# AD_Sensor_Module_-_SC.net
KiCad netlist of a schematic drawn in Altium Designer
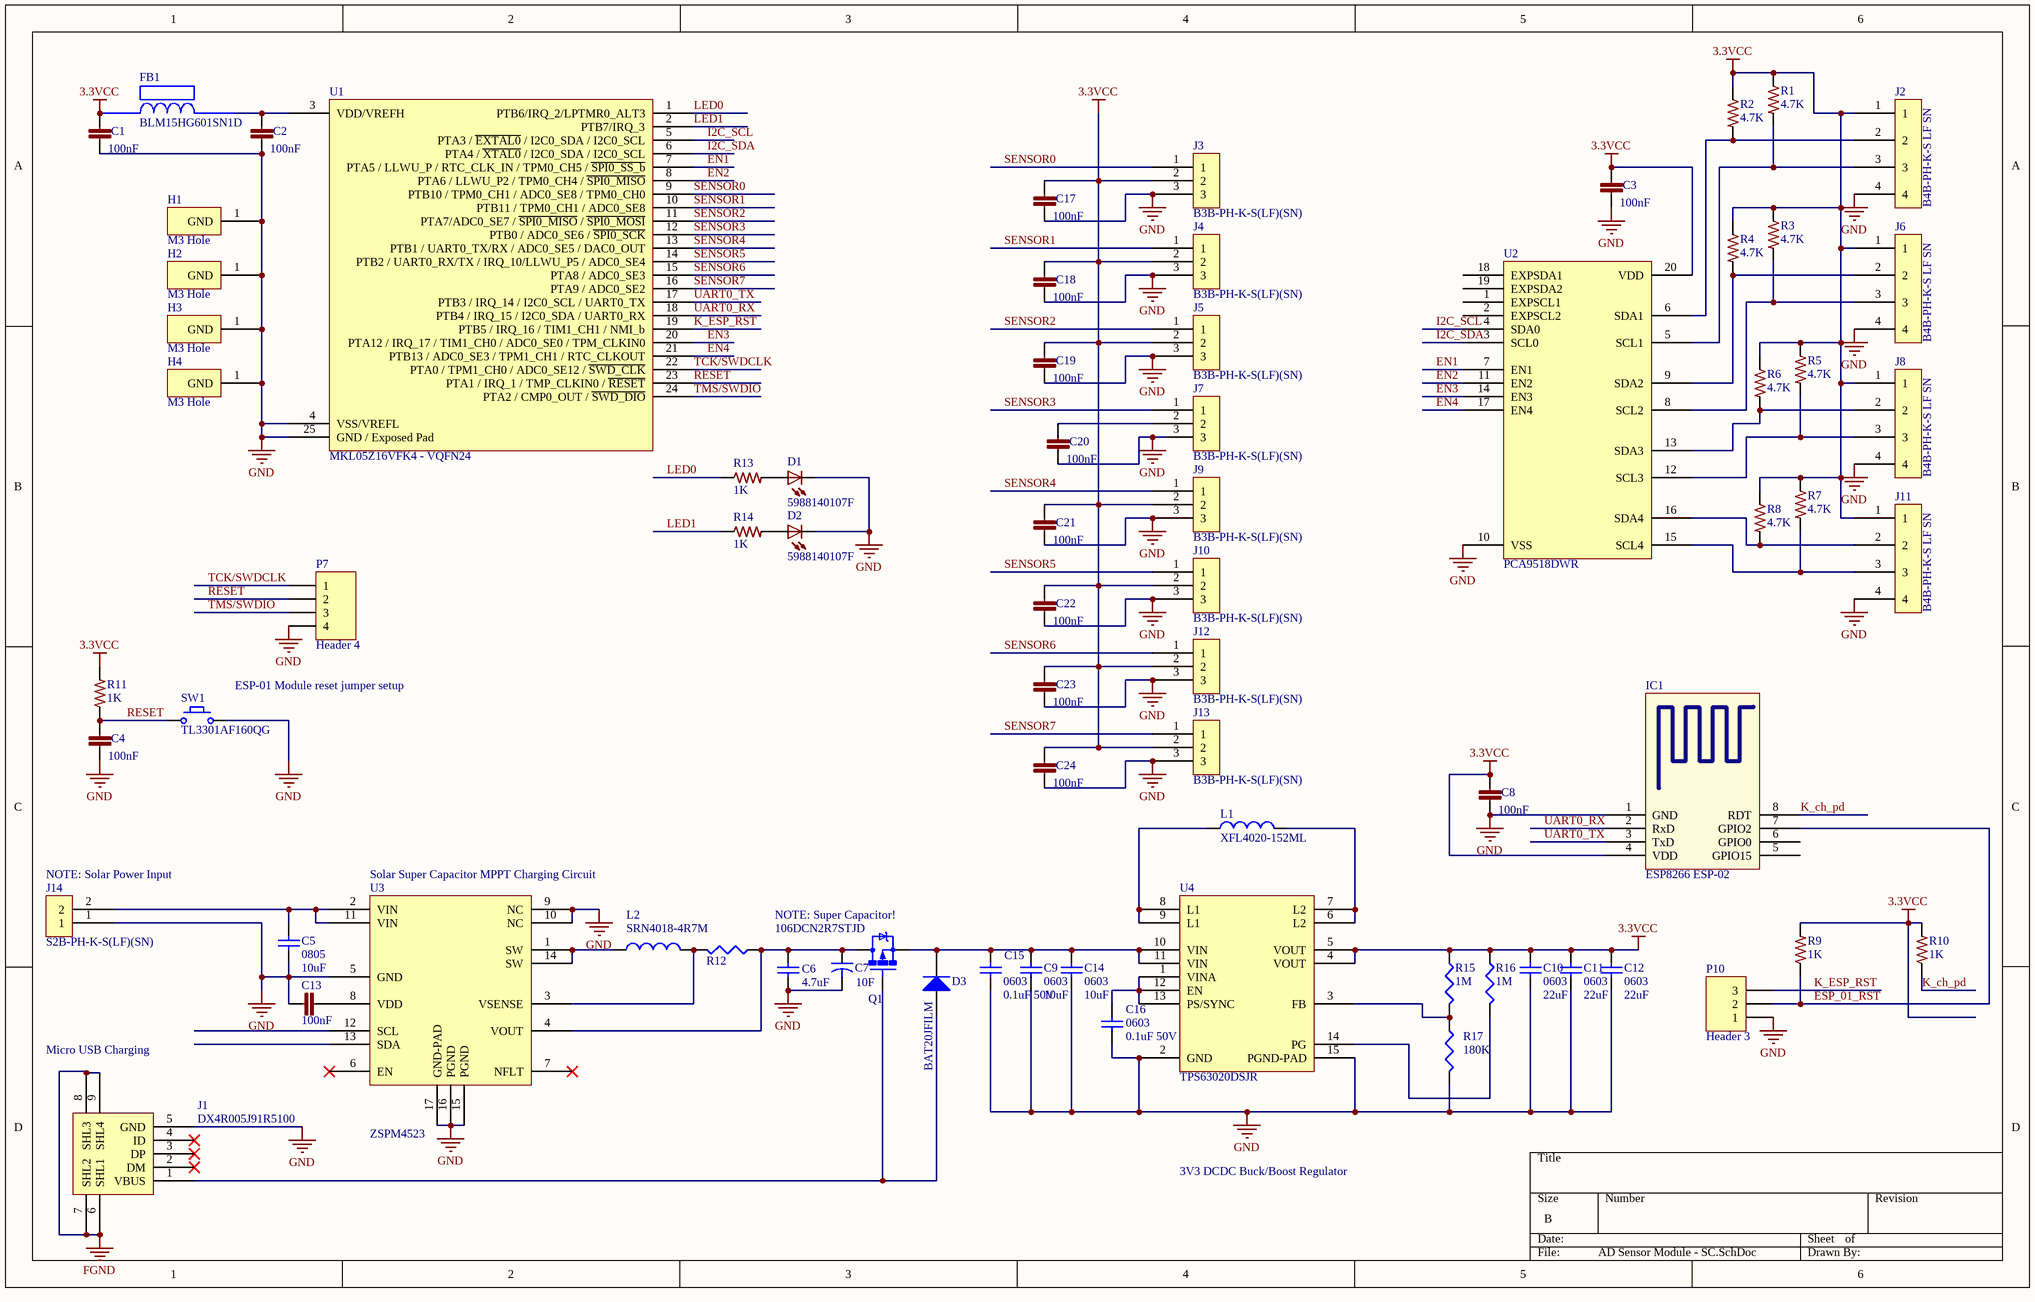
[diagram p0: AD Sensor Module - SC.SchDoc]

(export (version "E")
  (design (tool "Eeschema 10.0.6"))
  (components
    (comp (ref "C1")
      (value "100nF")
      (footprint "C0402")
      (description "CAP CER 0402 100nF 16V 10% X7R")
      (fields
        (field (name "MANUFACTURERPARTNUMBER") "GRM155R71C104KA88D")
        (field (name "PUBLISHER") "UltiMachine")
      )
      (libsource (lib "3Delight") (part "GRM155R71C104KA88D"))
    )
    (comp (ref "C2")
      (value "100nF")
      (footprint "C0402")
      (description "CAP CER 0402 100nF 16V 10% X7R")
      (fields
        (field (name "MANUFACTURERPARTNUMBER") "GRM155R71C104KA88D")
        (field (name "PUBLISHER") "UltiMachine")
      )
      (libsource (lib "3Delight") (part "GRM155R71C104KA88D"))
    )
    (comp (ref "C3")
      (value "100nF")
      (footprint "C0402")
      (description "CAP CER 0402 100nF 16V 10% X7R")
      (fields
        (field (name "MANUFACTURERPARTNUMBER") "GRM155R71C104KA88D")
        (field (name "PUBLISHER") "UltiMachine")
      )
      (libsource (lib "3Delight") (part "GRM155R71C104KA88D"))
    )
    (comp (ref "C4")
      (value "100nF")
      (footprint "C0402")
      (description "CAP CER 0402 100nF 16V 10% X7R")
      (fields
        (field (name "MANUFACTURERPARTNUMBER") "GRM155R71C104KA88D")
        (field (name "PUBLISHER") "UltiMachine")
      )
      (libsource (lib "3Delight") (part "GRM155R71C104KA88D"))
    )
    (comp (ref "C5")
      (value "0805")
      (footprint "C0805")
      (description "CAP CER 10UF 10V X5R 0805")
      (fields
        (field (name "MFR") "Samsung Electro-Mechanics America, Inc.")
        (field (name "TOLERANCE") "10%")
        (field (name "ALTIUM_VALUE") "10uF")
        (field (name "DESIGNER") "Adam Vadala-Roth")
      )
      (libsource (lib "Sensor Package") (part "CL21A106KPCLQNC"))
    )
    (comp (ref "C6")
      (value "4.7uF")
      (footprint "C0805")
      (description "CAP CER 4.7UF 10V Y5V 0805")
      (fields
        (field (name "MFR") "Samsung Electro-Mechanics America, Inc.")
        (field (name "TOLERANCE") "20%")
        (field (name "DESIGNER") "Adam Vadala-Roth")
      )
      (libsource (lib "Sensor Package") (part "CL21F475ZPFNNNE"))
    )
    (comp (ref "C7")
      (value "106DCN2R7STJD")
      (footprint "106DCN2R7STJD")
      (description "CAP 10F -20%, +50% 2.7V T/H")
      (fields
        (field (name "MFR") "Illinois Capacitor")
        (field (name "TOLERANCE") "20%")
        (field (name "ALTIUM_VALUE") "10F")
        (field (name "DESIGNER") "Adam Vadala-Roth")
      )
      (libsource (lib "Sensor Package") (part "106DCN2R7STJD"))
    )
    (comp (ref "C8")
      (value "100nF")
      (footprint "C0402")
      (description "CAP CER 0402 100nF 16V 10% X7R")
      (fields
        (field (name "MANUFACTURERPARTNUMBER") "GRM155R71C104KA88D")
        (field (name "PUBLISHER") "UltiMachine")
      )
      (libsource (lib "3Delight") (part "GRM155R71C104KA88D"))
    )
    (comp (ref "C9")
      (value "0603")
      (footprint "C0603")
      (description "CAP CER 10UF 6.3V X5R 0603")
      (fields
        (field (name "MFR") "Samsung Electro-Mechanics America, Inc.")
        (field (name "TOLERANCE") "10%")
        (field (name "ALTIUM_VALUE") "10uF")
        (field (name "DESIGNER") "Adam Vadala-Roth")
      )
      (libsource (lib "Sensor Package") (part "CL10A106KQ8NNNC"))
    )
    (comp (ref "C10")
      (value "0603")
      (footprint "C0603")
      (description "CAP CER 22UF 6.3V X5R 0603")
      (fields
        (field (name "MFR") "Samsung Electro-Mechanics America, Inc.")
        (field (name "TOLERANCE") "10%")
        (field (name "ALTIUM_VALUE") "22uF")
        (field (name "DESIGNER") "Adam Vadala-Roth")
      )
      (libsource (lib "Sensor Package") (part "CL10A226KQ8NRNE"))
    )
    (comp (ref "C11")
      (value "0603")
      (footprint "C0603")
      (description "CAP CER 22UF 6.3V X5R 0603")
      (fields
        (field (name "MFR") "Samsung Electro-Mechanics America, Inc.")
        (field (name "TOLERANCE") "10%")
        (field (name "ALTIUM_VALUE") "22uF")
        (field (name "DESIGNER") "Adam Vadala-Roth")
      )
      (libsource (lib "Sensor Package") (part "CL10A226KQ8NRNE"))
    )
    (comp (ref "C12")
      (value "0603")
      (footprint "C0603")
      (description "CAP CER 22UF 6.3V X5R 0603")
      (fields
        (field (name "MFR") "Samsung Electro-Mechanics America, Inc.")
        (field (name "TOLERANCE") "10%")
        (field (name "ALTIUM_VALUE") "22uF")
        (field (name "DESIGNER") "Adam Vadala-Roth")
      )
      (libsource (lib "Sensor Package") (part "CL10A226KQ8NRNE"))
    )
    (comp (ref "C13")
      (value "100nF")
      (footprint "C0402")
      (description "CAP CER 0402 100nF 16V 10% X7R")
      (fields
        (field (name "MANUFACTURERPARTNUMBER") "GRM155R71C104KA88D")
        (field (name "PUBLISHER") "UltiMachine")
      )
      (libsource (lib "") (part "GRM155R71C104KA88D_1"))
    )
    (comp (ref "C14")
      (value "0603")
      (footprint "C0603")
      (description "CAP CER 10UF 6.3V X5R 0603")
      (fields
        (field (name "MFR") "Samsung Electro-Mechanics America, Inc.")
        (field (name "TOLERANCE") "10%")
        (field (name "ALTIUM_VALUE") "10uF")
        (field (name "DESIGNER") "Adam Vadala-Roth")
      )
      (libsource (lib "Sensor Package") (part "CL10A106KQ8NNNC"))
    )
    (comp (ref "C15")
      (value "0603")
      (footprint "C0603")
      (description "CAP CER 0.1UF 50V 10% X7R 0603")
      (fields
        (field (name "MFR PART #") "CL10B104KB8SFNC")
        (field (name "MFR") "Samsung")
        (field (name "ALTIUM_VALUE") "0.1uF 50V")
      )
      (libsource (lib "Sensor Package") (part "CL10B104KB8SFNC"))
    )
    (comp (ref "C16")
      (value "0603")
      (footprint "C0603")
      (description "CAP CER 0.1UF 50V 10% X7R 0603")
      (fields
        (field (name "MFR PART #") "CL10B104KB8SFNC")
        (field (name "MFR") "Samsung")
        (field (name "ALTIUM_VALUE") "0.1uF 50V")
      )
      (libsource (lib "Sensor Package") (part "CL10B104KB8SFNC"))
    )
    (comp (ref "C17")
      (value "100nF")
      (footprint "C0402")
      (description "CAP CER 0402 100nF 16V 10% X7R")
      (fields
        (field (name "MANUFACTURERPARTNUMBER") "GRM155R71C104KA88D")
        (field (name "PUBLISHER") "UltiMachine")
      )
      (libsource (lib "3Delight") (part "GRM155R71C104KA88D"))
    )
    (comp (ref "C18")
      (value "100nF")
      (footprint "C0402")
      (description "CAP CER 0402 100nF 16V 10% X7R")
      (fields
        (field (name "MANUFACTURERPARTNUMBER") "GRM155R71C104KA88D")
        (field (name "PUBLISHER") "UltiMachine")
      )
      (libsource (lib "3Delight") (part "GRM155R71C104KA88D"))
    )
    (comp (ref "C19")
      (value "100nF")
      (footprint "C0402")
      (description "CAP CER 0402 100nF 16V 10% X7R")
      (fields
        (field (name "MANUFACTURERPARTNUMBER") "GRM155R71C104KA88D")
        (field (name "PUBLISHER") "UltiMachine")
      )
      (libsource (lib "3Delight") (part "GRM155R71C104KA88D"))
    )
    (comp (ref "C20")
      (value "100nF")
      (footprint "C0402")
      (description "CAP CER 0402 100nF 16V 10% X7R")
      (fields
        (field (name "MANUFACTURERPARTNUMBER") "GRM155R71C104KA88D")
        (field (name "PUBLISHER") "UltiMachine")
      )
      (libsource (lib "3Delight") (part "GRM155R71C104KA88D"))
    )
    (comp (ref "C21")
      (value "100nF")
      (footprint "C0402")
      (description "CAP CER 0402 100nF 16V 10% X7R")
      (fields
        (field (name "MANUFACTURERPARTNUMBER") "GRM155R71C104KA88D")
        (field (name "PUBLISHER") "UltiMachine")
      )
      (libsource (lib "3Delight") (part "GRM155R71C104KA88D"))
    )
    (comp (ref "C22")
      (value "100nF")
      (footprint "C0402")
      (description "CAP CER 0402 100nF 16V 10% X7R")
      (fields
        (field (name "MANUFACTURERPARTNUMBER") "GRM155R71C104KA88D")
        (field (name "PUBLISHER") "UltiMachine")
      )
      (libsource (lib "3Delight") (part "GRM155R71C104KA88D"))
    )
    (comp (ref "C23")
      (value "100nF")
      (footprint "C0402")
      (description "CAP CER 0402 100nF 16V 10% X7R")
      (fields
        (field (name "MANUFACTURERPARTNUMBER") "GRM155R71C104KA88D")
        (field (name "PUBLISHER") "UltiMachine")
      )
      (libsource (lib "3Delight") (part "GRM155R71C104KA88D"))
    )
    (comp (ref "C24")
      (value "100nF")
      (footprint "C0402")
      (description "CAP CER 0402 100nF 16V 10% X7R")
      (fields
        (field (name "MANUFACTURERPARTNUMBER") "GRM155R71C104KA88D")
        (field (name "PUBLISHER") "UltiMachine")
      )
      (libsource (lib "3Delight") (part "GRM155R71C104KA88D"))
    )
    (comp (ref "D1")
      (value "5988140107F")
      (footprint "LED2012120")
      (description "LED 0805 Yellow")
      (fields (field (name "PUBLISHER") "UltiMachine"))
      (libsource (lib "Tigershark3D") (part "5988140107F"))
    )
    (comp (ref "D2")
      (value "5988140107F")
      (footprint "LED2012120")
      (description "LED 0805 Yellow")
      (fields (field (name "PUBLISHER") "UltiMachine"))
      (libsource (lib "Tigershark3D") (part "5988140107F"))
    )
    (comp (ref "D3")
      (value "BAT20JFILM")
      (footprint "BAT20JFILM - DIOM1712X11N")
      (description "DIODE SCHOTTKY 23V 1A SOD323")
      (fields
        (field (name "MFR") "ST Microelectronics")
        (field (name "PUBLISHER") "Altium Limited")
        (field (name "DESIGNER") "Adam J Valala-Roth")
      )
      (libsource (lib "Sensor Package") (part "BAT20JFILM"))
    )
    (comp (ref "FB1")
      (value "BLM15HG601SN1D")
      (footprint "BLM18PG121SN1D")
      (libsource (lib "Sensor Package") (part "BLM15HG601SN1D"))
    )
    (comp (ref "H1")
      (value "M3 Hole")
      (footprint "Hole-3mm")
      (description "3mm Hole")
      (libsource (lib "Sensor Package") (part "Hole"))
    )
    (comp (ref "H2")
      (value "M3 Hole")
      (footprint "Hole-3mm")
      (description "3mm Hole")
      (libsource (lib "Sensor Package") (part "Hole"))
    )
    (comp (ref "H3")
      (value "M3 Hole")
      (footprint "Hole-3mm")
      (description "3mm Hole")
      (libsource (lib "Sensor Package") (part "Hole"))
    )
    (comp (ref "H4")
      (value "M3 Hole")
      (footprint "Hole-3mm")
      (description "3mm Hole")
      (libsource (lib "Sensor Package") (part "Hole"))
    )
    (comp (ref "IC1")
      (value "ESP8266 ESP-02")
      (footprint "ESP8266 ESP-02")
      (libsource (lib "ESP8266") (part "ESP8266 ESP-02"))
    )
    (comp (ref "J1")
      (value "DX4R005J91R5100")
      (footprint "Micro USB Circular Holes Only")
      (description "Micro USB Jack B")
      (libsource (lib "Sensor Package") (part "Micro USB"))
    )
    (comp (ref "J2")
      (value "B4B-PH-K-S LF SN")
      (footprint "B4B-PH-K-S(LF)(SN)")
      (description "CONN HEADER PH TOP 4POS 2MM")
      (fields (field (name "MFR") "JST") (field (name "DESIGNER") "Adam Vadala-Roth"))
      (libsource (lib "Sensor Package") (part "B4B-PH-K-S LF SN"))
    )
    (comp (ref "J3")
      (value "B3B-PH-K-S(LF)(SN)")
      (footprint "B3B-PH-K-S(LF)(SN)")
      (description "CONN HEADER PH TOP 3POS 2MM")
      (fields (field (name "MFR") "JST") (field (name "DESIGNER") "Adam Vadala-Roth"))
      (libsource (lib "Sensor Package") (part "B3B-PH-K-S(LF)(SN)"))
    )
    (comp (ref "J4")
      (value "B3B-PH-K-S(LF)(SN)")
      (footprint "B3B-PH-K-S(LF)(SN)")
      (description "CONN HEADER PH TOP 3POS 2MM")
      (fields (field (name "MFR") "JST") (field (name "DESIGNER") "Adam Vadala-Roth"))
      (libsource (lib "Sensor Package") (part "B3B-PH-K-S(LF)(SN)"))
    )
    (comp (ref "J5")
      (value "B3B-PH-K-S(LF)(SN)")
      (footprint "B3B-PH-K-S(LF)(SN)")
      (description "CONN HEADER PH TOP 3POS 2MM")
      (fields (field (name "MFR") "JST") (field (name "DESIGNER") "Adam Vadala-Roth"))
      (libsource (lib "Sensor Package") (part "B3B-PH-K-S(LF)(SN)"))
    )
    (comp (ref "J6")
      (value "B4B-PH-K-S LF SN")
      (footprint "B4B-PH-K-S(LF)(SN)")
      (description "CONN HEADER PH TOP 4POS 2MM")
      (fields (field (name "MFR") "JST") (field (name "DESIGNER") "Adam Vadala-Roth"))
      (libsource (lib "Sensor Package") (part "B4B-PH-K-S LF SN"))
    )
    (comp (ref "J7")
      (value "B3B-PH-K-S(LF)(SN)")
      (footprint "B3B-PH-K-S(LF)(SN)")
      (description "CONN HEADER PH TOP 3POS 2MM")
      (fields (field (name "MFR") "JST") (field (name "DESIGNER") "Adam Vadala-Roth"))
      (libsource (lib "Sensor Package") (part "B3B-PH-K-S(LF)(SN)"))
    )
    (comp (ref "J8")
      (value "B4B-PH-K-S LF SN")
      (footprint "B4B-PH-K-S(LF)(SN)")
      (description "CONN HEADER PH TOP 4POS 2MM")
      (fields (field (name "MFR") "JST") (field (name "DESIGNER") "Adam Vadala-Roth"))
      (libsource (lib "Sensor Package") (part "B4B-PH-K-S LF SN"))
    )
    (comp (ref "J9")
      (value "B3B-PH-K-S(LF)(SN)")
      (footprint "B3B-PH-K-S(LF)(SN)")
      (description "CONN HEADER PH TOP 3POS 2MM")
      (fields (field (name "MFR") "JST") (field (name "DESIGNER") "Adam Vadala-Roth"))
      (libsource (lib "Sensor Package") (part "B3B-PH-K-S(LF)(SN)"))
    )
    (comp (ref "J10")
      (value "B3B-PH-K-S(LF)(SN)")
      (footprint "B3B-PH-K-S(LF)(SN)")
      (description "CONN HEADER PH TOP 3POS 2MM")
      (fields (field (name "MFR") "JST") (field (name "DESIGNER") "Adam Vadala-Roth"))
      (libsource (lib "Sensor Package") (part "B3B-PH-K-S(LF)(SN)"))
    )
    (comp (ref "J11")
      (value "B4B-PH-K-S LF SN")
      (footprint "B4B-PH-K-S(LF)(SN)")
      (description "CONN HEADER PH TOP 4POS 2MM")
      (fields (field (name "MFR") "JST") (field (name "DESIGNER") "Adam Vadala-Roth"))
      (libsource (lib "Sensor Package") (part "B4B-PH-K-S LF SN"))
    )
    (comp (ref "J12")
      (value "B3B-PH-K-S(LF)(SN)")
      (footprint "B3B-PH-K-S(LF)(SN)")
      (description "CONN HEADER PH TOP 3POS 2MM")
      (fields (field (name "MFR") "JST") (field (name "DESIGNER") "Adam Vadala-Roth"))
      (libsource (lib "Sensor Package") (part "B3B-PH-K-S(LF)(SN)"))
    )
    (comp (ref "J13")
      (value "B3B-PH-K-S(LF)(SN)")
      (footprint "B3B-PH-K-S(LF)(SN)")
      (description "CONN HEADER PH TOP 3POS 2MM")
      (fields (field (name "MFR") "JST") (field (name "DESIGNER") "Adam Vadala-Roth"))
      (libsource (lib "Sensor Package") (part "B3B-PH-K-S(LF)(SN)"))
    )
    (comp (ref "J14")
      (value "S2B-PH-K-S(LF)(SN)")
      (footprint "S2B-PH-K-S(LF)(SN)")
      (description "CONN HEADER PH SIDE 2POS 2MM")
      (fields (field (name "MFR") "JST") (field (name "DESIGNER") "Adam Vadala-Roth"))
      (libsource (lib "Sensor Package") (part "S2B-PH-K-S(LF)(SN)"))
    )
    (comp (ref "L1")
      (value "XFL4020-152ML")
      (footprint "XFL4020-152ML - INDP4040X21N")
      (fields (field (name "MFR") "Coilcraft") (field (name "DESIGNER") "Adam Vadala-Roth"))
      (libsource (lib "Sensor Package") (part "XFL4020-152ML"))
    )
    (comp (ref "L2")
      (value "SRN4018-4R7M")
      (footprint "SRN4018-4R7M - INDP4040X18N")
      (description "FIXED IND 4.7UH 1.9A 84 MOHM SMD")
      (fields
        (field (name "MFR") "Bourns")
        (field (name "TOLERANCE") "+/-20%")
        (field (name "DESIGNER") "Adam Vadala-Roth")
      )
      (libsource (lib "Sensor Package") (part "SRN4018-4R7M"))
    )
    (comp (ref "P7")
      (value "Header 4")
      (footprint "HDR1X4")
      (description "Header, 4-Pin")
      (fields (field (name "PUBLISHER") "Altium Limited"))
      (libsource (lib "Miscellaneous Connectors") (part "Header 4"))
    )
    (comp (ref "P10")
      (value "Header 3")
      (footprint "HDR1X3")
      (description "Header, 3-Pin")
      (fields (field (name "PUBLISHER") "Altium Limited"))
      (libsource (lib "Miscellaneous Connectors") (part "Header 3"))
    )
    (comp (ref "Q1")
      (value "DMG2307L-7")
      (footprint "DMG2307L-7 - SOT92P240X102-3N")
      (description "MOSFET P-CH 30V 2.5A SOT-23")
      (fields (field (name "MFR") "Diodes Incorporated") (field (name "PUBLISHER") "Adam Vadala-Roth"))
      (libsource (lib "Sensor Package") (part "DMG2307L-7"))
    )
    (comp (ref "R1")
      (value "4.7K")
      (footprint "R0603")
      (description "RES 0603 4.7K 100mW 1%")
      (fields (field (name "MANUFACTURERPARTNUMBER") "ERJ3EKF4701V") (field (name "PUBLISHER") "UltiMachine"))
      (libsource (lib "Tigershark3D") (part "ERJ3EKF4701V"))
    )
    (comp (ref "R2")
      (value "4.7K")
      (footprint "R0603")
      (description "RES 0603 4.7K 100mW 1%")
      (fields (field (name "MANUFACTURERPARTNUMBER") "ERJ3EKF4701V") (field (name "PUBLISHER") "UltiMachine"))
      (libsource (lib "Tigershark3D") (part "ERJ3EKF4701V"))
    )
    (comp (ref "R3")
      (value "4.7K")
      (footprint "R0603")
      (description "RES 0603 4.7K 100mW 1%")
      (fields (field (name "MANUFACTURERPARTNUMBER") "ERJ3EKF4701V") (field (name "PUBLISHER") "UltiMachine"))
      (libsource (lib "Tigershark3D") (part "ERJ3EKF4701V"))
    )
    (comp (ref "R4")
      (value "4.7K")
      (footprint "R0603")
      (description "RES 0603 4.7K 100mW 1%")
      (fields (field (name "MANUFACTURERPARTNUMBER") "ERJ3EKF4701V") (field (name "PUBLISHER") "UltiMachine"))
      (libsource (lib "Tigershark3D") (part "ERJ3EKF4701V"))
    )
    (comp (ref "R5")
      (value "4.7K")
      (footprint "R0603")
      (description "RES 0603 4.7K 100mW 1%")
      (fields (field (name "MANUFACTURERPARTNUMBER") "ERJ3EKF4701V") (field (name "PUBLISHER") "UltiMachine"))
      (libsource (lib "Tigershark3D") (part "ERJ3EKF4701V"))
    )
    (comp (ref "R6")
      (value "4.7K")
      (footprint "R0603")
      (description "RES 0603 4.7K 100mW 1%")
      (fields (field (name "MANUFACTURERPARTNUMBER") "ERJ3EKF4701V") (field (name "PUBLISHER") "UltiMachine"))
      (libsource (lib "Tigershark3D") (part "ERJ3EKF4701V"))
    )
    (comp (ref "R7")
      (value "4.7K")
      (footprint "R0603")
      (description "RES 0603 4.7K 100mW 1%")
      (fields (field (name "MANUFACTURERPARTNUMBER") "ERJ3EKF4701V") (field (name "PUBLISHER") "UltiMachine"))
      (libsource (lib "Tigershark3D") (part "ERJ3EKF4701V"))
    )
    (comp (ref "R8")
      (value "4.7K")
      (footprint "R0603")
      (description "RES 0603 4.7K 100mW 1%")
      (fields (field (name "MANUFACTURERPARTNUMBER") "ERJ3EKF4701V") (field (name "PUBLISHER") "UltiMachine"))
      (libsource (lib "Tigershark3D") (part "ERJ3EKF4701V"))
    )
    (comp (ref "R9")
      (value "1K")
      (footprint "R0603")
      (description "RES 0603 1K 100mW 1%")
      (fields
        (field (name "MANUFACTURERPARTNUMBER") "ERJ-3EKF1001V")
        (field (name "PUBLISHER") "UltiMachine")
      )
      (libsource (lib "3Delight") (part "ERJ-3EKF1001V"))
    )
    (comp (ref "R10")
      (value "1K")
      (footprint "R0603")
      (description "RES 0603 1K 100mW 1%")
      (fields
        (field (name "MANUFACTURERPARTNUMBER") "ERJ-3EKF1001V")
        (field (name "PUBLISHER") "UltiMachine")
      )
      (libsource (lib "3Delight") (part "ERJ-3EKF1001V"))
    )
    (comp (ref "R11")
      (value "1K")
      (footprint "R0603")
      (description "RES 0603 1K 100mW 1%")
      (fields
        (field (name "MANUFACTURERPARTNUMBER") "ERJ-3EKF1001V")
        (field (name "PUBLISHER") "UltiMachine")
      )
      (libsource (lib "3Delight") (part "ERJ-3EKF1001V"))
    )
    (comp (ref "R12")
      (value "RU3216FR051CS")
      (footprint "R1206")
      (description "RES SMD 0.051 OHM 1% 1/2W 1206 Current Sense Resistor*")
      (fields
        (field (name "MFR") "Samsung Electro-Mechanics America, Inc.")
        (field (name "TOLERANCE") "1%")
        (field (name "DESIGNER") "Adam Vadala-Roth")
      )
      (libsource (lib "Sensor Package") (part "RU3216FR051CS"))
    )
    (comp (ref "R13")
      (value "1K")
      (footprint "R0603")
      (description "RES 0603 1K 100mW 1%")
      (fields
        (field (name "MANUFACTURERPARTNUMBER") "ERJ-3EKF1001V")
        (field (name "PUBLISHER") "UltiMachine")
      )
      (libsource (lib "Tigershark3D") (part "ERJ-3EKF1001V"))
    )
    (comp (ref "R14")
      (value "1K")
      (footprint "R0603")
      (description "RES 0603 1K 100mW 1%")
      (fields
        (field (name "MANUFACTURERPARTNUMBER") "ERJ-3EKF1001V")
        (field (name "PUBLISHER") "UltiMachine")
      )
      (libsource (lib "Tigershark3D") (part "ERJ-3EKF1001V"))
    )
    (comp (ref "R15")
      (value "1M")
      (footprint "R0603")
      (description "RES SMD 1M OHM 1% 1/10W 0603")
      (fields
        (field (name "MFR") "Samsung Electro-Mechanics America, Inc.")
        (field (name "TOLERANCE") "1%")
        (field (name "DESIGNER") "Adam Vadala-Roth")
      )
      (libsource (lib "Sensor Package") (part "RC1608F105CS"))
    )
    (comp (ref "R16")
      (value "1M")
      (footprint "R0603")
      (description "RES SMD 1M OHM 1% 1/10W 0603")
      (fields
        (field (name "MFR") "Samsung Electro-Mechanics America, Inc.")
        (field (name "TOLERANCE") "1%")
        (field (name "DESIGNER") "Adam Vadala-Roth")
      )
      (libsource (lib "Sensor Package") (part "RC1608F105CS"))
    )
    (comp (ref "R17")
      (value "180K")
      (footprint "R0603")
      (description "RES SMD 180K OHM 1% 1/10W 060")
      (fields
        (field (name "MFR") "Samsung Electro-Mechanics America, Inc.")
        (field (name "TOLERANCE") "1%")
        (field (name "DESIGNER") "Adam Vadala-Roth")
      )
      (libsource (lib "Sensor Package") (part "RC1608F184CS"))
    )
    (comp (ref "SW1")
      (value "TL3301AF160QG")
      (footprint "TL3301AF160QG")
      (libsource (lib "MongoosMini") (part "TL3301AF160QG"))
    )
    (comp (ref "U1")
      (value "MKL05Z16VFK4 - VQFN24")
      (footprint "98ASA00474D")
      (description "ARM Cortex M0+")
      (libsource (lib "Encoder Fin") (part "MKL05Z16VFK4 - 24 Pin VQFN"))
    )
    (comp (ref "U2")
      (value "PCA9518DWR")
      (footprint "PCA9518DWR")
      (description "IC EXPANDABLE 5CH I2C HUB 20SOIC")
      (fields (field (name "MFR") "Ti"))
      (libsource (lib "Sensor Package") (part "PCA9518DWR"))
    )
    (comp (ref "U3")
      (value "ZSPM4523")
      (footprint "ZSPM4523 - QFN65P400X400X100_HS-17N")
      (description "ZSPM4523 Charge Controller")
      (fields (field (name "MFR") "ZMDI") (field (name "DESIGNER") "Adam J Vadala-Roth"))
      (libsource (lib "Sensor Package") (part "ZSPM4523"))
    )
    (comp (ref "U4")
      (value "TPS63020DSJR")
      (footprint "TPS63020 - QFN50P400X300X100-22N")
      (description "IC REG BUCK BST ADJ 3.5A 14VSON")
      (fields (field (name "MFR") "Texas Instruments") (field (name "DESIGNER") "Adam J Vadala-Roth"))
      (libsource (lib "Sensor Package") (part "TPS63020"))
    )
  )
  (nets
    (net (code "1") (name "/EN1") (class "Default")
      (node (ref "U1") (pin "7") (pinfunction "PTA5_/_LLWU_P_/_RTC_CLK_IN_/_TPM0_CH5_/_~{SPI0_SS_b}_7") (pintype "passive"))
      (node (ref "U2") (pin "7") (pinfunction "EN1_7") (pintype "passive"))
    )
    (net (code "2") (name "/EN2") (class "Default")
      (node (ref "U1") (pin "8") (pinfunction "PTA6_/_LLWU_P2_/_TPM0_CH4_/_~{SPI0_MISO}_8") (pintype "passive"))
      (node (ref "U2") (pin "11") (pinfunction "EN2_11") (pintype "passive"))
    )
    (net (code "3") (name "/EN3") (class "Default")
      (node (ref "U1") (pin "20") (pinfunction "PTA12_/_IRQ_17_/_TIM1_CH0_/_ADC0_SE0_/_TPM_CLKIN0_20") (pintype "passive"))
      (node (ref "U2") (pin "14") (pinfunction "EN3_14") (pintype "passive"))
    )
    (net (code "4") (name "/EN4") (class "Default")
      (node (ref "U1") (pin "21") (pinfunction "PTB13_/_ADC0_SE3_/_TPM1_CH1_/_RTC_CLKOUT_21") (pintype "passive"))
      (node (ref "U2") (pin "17") (pinfunction "EN4_17") (pintype "passive"))
    )
    (net (code "5") (name "/ESP_01_RST") (class "Default")
      (node (ref "IC1") (pin "7") (pinfunction "GPIO2_7") (pintype "passive"))
      (node (ref "P10") (pin "2") (pinfunction "2_2") (pintype "passive"))
      (node (ref "R9") (pin "1") (pinfunction "1_1") (pintype "passive"))
    )
    (net (code "6") (name "/I2C_SCL") (class "Default")
      (node (ref "U1") (pin "5") (pinfunction "PTA3_/_~{EXTAL0}_/_I2C0_SDA_/_I2C0_SCL_5") (pintype "passive"))
      (node (ref "U2") (pin "4") (pinfunction "SDA0_4") (pintype "passive"))
    )
    (net (code "7") (name "/I2C_SDA") (class "Default")
      (node (ref "U1") (pin "6") (pinfunction "PTA4_/_~{XTAL0}_/_I2C0_SDA_/_I2C0_SCL_6") (pintype "passive"))
      (node (ref "U2") (pin "3") (pinfunction "SCL0_3") (pintype "passive"))
    )
    (net (code "8") (name "/K_ESP_RST") (class "Default")
      (node (ref "P10") (pin "3") (pinfunction "3_3") (pintype "passive"))
      (node (ref "U1") (pin "19") (pinfunction "PTB5_/_IRQ_16_/_TIM1_CH1_/_NMI_b_19") (pintype "passive"))
    )
    (net (code "9") (name "/K_ch_pd") (class "Default")
      (node (ref "IC1") (pin "8") (pinfunction "RDT_8") (pintype "passive"))
      (node (ref "R10") (pin "1") (pinfunction "1_1") (pintype "passive"))
    )
    (net (code "10") (name "/LED0") (class "Default")
      (node (ref "R13") (pin "1") (pinfunction "1_1") (pintype "passive"))
      (node (ref "U1") (pin "1") (pinfunction "PTB6/IRQ_2/LPTMR0_ALT3_1") (pintype "passive"))
    )
    (net (code "11") (name "/LED1") (class "Default")
      (node (ref "R14") (pin "1") (pinfunction "1_1") (pintype "passive"))
      (node (ref "U1") (pin "2") (pinfunction "PTB7/IRQ_3_2") (pintype "passive"))
    )
    (net (code "12") (name "/RESET") (class "Default")
      (node (ref "C4") (pin "1") (pinfunction "1_1") (pintype "passive"))
      (node (ref "P7") (pin "2") (pinfunction "2_2") (pintype "passive"))
      (node (ref "R11") (pin "1") (pinfunction "1_1") (pintype "passive"))
      (node (ref "SW1") (pin "1") (pintype "passive"))
      (node (ref "U1") (pin "23") (pinfunction "PTA1_/_IRQ_1_/_TMP_CLKIN0_/_~{RESET}_23") (pintype "passive"))
    )
    (net (code "13") (name "/SENSOR0") (class "Default")
      (node (ref "J3") (pin "1") (pinfunction "1_1") (pintype "passive"))
      (node (ref "U1") (pin "9") (pinfunction "PTB10_/_TPM0_CH1_/_ADC0_SE8_/_TPM0_CH0_9") (pintype "passive"))
    )
    (net (code "14") (name "/SENSOR1") (class "Default")
      (node (ref "J4") (pin "1") (pinfunction "1_1") (pintype "passive"))
      (node (ref "U1") (pin "10") (pinfunction "PTB11_/_TPM0_CH1_/_ADC0_SE8_10") (pintype "passive"))
    )
    (net (code "15") (name "/SENSOR2") (class "Default")
      (node (ref "J5") (pin "1") (pinfunction "1_1") (pintype "passive"))
      (node (ref "U1") (pin "11") (pinfunction "PTA7/ADC0_SE7_/_~{SPI0_MISO}_/_~{SPI0_MOSI}_11") (pintype "passive"))
    )
    (net (code "16") (name "/SENSOR3") (class "Default")
      (node (ref "J7") (pin "1") (pinfunction "1_1") (pintype "passive"))
      (node (ref "U1") (pin "12") (pinfunction "PTB0_/_ADC0_SE6_/_~{SPI0_SCK}_12") (pintype "passive"))
    )
    (net (code "17") (name "/SENSOR4") (class "Default")
      (node (ref "J9") (pin "1") (pinfunction "1_1") (pintype "passive"))
      (node (ref "U1") (pin "13") (pinfunction "PTB1_/_UART0_TX/RX_/_ADC0_SE5_/_DAC0_OUT_13") (pintype "passive"))
    )
    (net (code "18") (name "/SENSOR5") (class "Default")
      (node (ref "J10") (pin "1") (pinfunction "1_1") (pintype "passive"))
      (node (ref "U1") (pin "14") (pinfunction "PTB2_/_UART0_RX/TX_/_IRQ_10/LLWU_P5_/_ADC0_SE4_14") (pintype "passive"))
    )
    (net (code "19") (name "/SENSOR6") (class "Default")
      (node (ref "J12") (pin "1") (pinfunction "1_1") (pintype "passive"))
      (node (ref "U1") (pin "15") (pinfunction "PTA8_/_ADC0_SE3_15") (pintype "passive"))
    )
    (net (code "20") (name "/SENSOR7") (class "Default")
      (node (ref "J13") (pin "1") (pinfunction "1_1") (pintype "passive"))
      (node (ref "U1") (pin "16") (pinfunction "PTA9_/_ADC0_SE2_16") (pintype "passive"))
    )
    (net (code "21") (name "/TCK{slash}SWDCLK") (class "Default")
      (node (ref "P7") (pin "1") (pinfunction "1_1") (pintype "passive"))
      (node (ref "U1") (pin "22") (pinfunction "PTA0_/_TPM1_CH0_/_ADC0_SE12_/_~{SWD_CLK}_22") (pintype "passive"))
    )
    (net (code "22") (name "/TMS{slash}SWDIO") (class "Default")
      (node (ref "P7") (pin "3") (pinfunction "3_3") (pintype "passive"))
      (node (ref "U1") (pin "24") (pinfunction "PTA2_/_CMP0_OUT_/_~{SWD_DIO}_24") (pintype "passive"))
    )
    (net (code "23") (name "/UART0_RX") (class "Default")
      (node (ref "IC1") (pin "2") (pinfunction "RxD_2") (pintype "passive"))
      (node (ref "U1") (pin "18") (pinfunction "PTB4_/_IRQ_15_/_I2C0_SDA_/_UART0_RX_18") (pintype "passive"))
    )
    (net (code "24") (name "/UART0_TX") (class "Default")
      (node (ref "IC1") (pin "3") (pinfunction "TxD_3") (pintype "passive"))
      (node (ref "U1") (pin "17") (pinfunction "PTB3_/_IRQ_14_/_I2C0_SCL_/_UART0_TX_17") (pintype "passive"))
    )
    (net (code "25") (name "3.3VCC") (class "Default")
      (node (ref "C1") (pin "1") (pinfunction "1_1") (pintype "passive"))
      (node (ref "C10") (pin "2") (pinfunction "2_2") (pintype "passive"))
      (node (ref "C11") (pin "2") (pinfunction "2_2") (pintype "passive"))
      (node (ref "C12") (pin "2") (pinfunction "2_2") (pintype "passive"))
      (node (ref "C17") (pin "1") (pinfunction "1_1") (pintype "passive"))
      (node (ref "C18") (pin "1") (pinfunction "1_1") (pintype "passive"))
      (node (ref "C19") (pin "1") (pinfunction "1_1") (pintype "passive"))
      (node (ref "C21") (pin "1") (pinfunction "1_1") (pintype "passive"))
      (node (ref "C22") (pin "1") (pinfunction "1_1") (pintype "passive"))
      (node (ref "C23") (pin "1") (pinfunction "1_1") (pintype "passive"))
      (node (ref "C24") (pin "1") (pinfunction "1_1") (pintype "passive"))
      (node (ref "C3") (pin "1") (pinfunction "1_1") (pintype "passive"))
      (node (ref "C8") (pin "1") (pinfunction "1_1") (pintype "passive"))
      (node (ref "FB1") (pin "1") (pinfunction "1_1") (pintype "passive"))
      (node (ref "IC1") (pin "4") (pinfunction "VDD_4") (pintype "passive"))
      (node (ref "J10") (pin "2") (pinfunction "2_2") (pintype "passive"))
      (node (ref "J11") (pin "1") (pinfunction "1_1") (pintype "passive"))
      (node (ref "J12") (pin "2") (pinfunction "2_2") (pintype "passive"))
      (node (ref "J13") (pin "2") (pinfunction "2_2") (pintype "passive"))
      (node (ref "J2") (pin "1") (pinfunction "1_1") (pintype "passive"))
      (node (ref "J3") (pin "2") (pinfunction "2_2") (pintype "passive"))
      (node (ref "J4") (pin "2") (pinfunction "2_2") (pintype "passive"))
      (node (ref "J5") (pin "2") (pinfunction "2_2") (pintype "passive"))
      (node (ref "J6") (pin "1") (pinfunction "1_1") (pintype "passive"))
      (node (ref "J8") (pin "1") (pinfunction "1_1") (pintype "passive"))
      (node (ref "J9") (pin "2") (pinfunction "2_2") (pintype "passive"))
      (node (ref "R1") (pin "1") (pinfunction "1_1") (pintype "passive"))
      (node (ref "R10") (pin "2") (pinfunction "2_2") (pintype "passive"))
      (node (ref "R11") (pin "2") (pinfunction "2_2") (pintype "passive"))
      (node (ref "R15") (pin "1") (pinfunction "1_1") (pintype "passive"))
      (node (ref "R16") (pin "1") (pinfunction "1_1") (pintype "passive"))
      (node (ref "R2") (pin "1") (pinfunction "1_1") (pintype "passive"))
      (node (ref "R3") (pin "1") (pinfunction "1_1") (pintype "passive"))
      (node (ref "R4") (pin "1") (pinfunction "1_1") (pintype "passive"))
      (node (ref "R5") (pin "1") (pinfunction "1_1") (pintype "passive"))
      (node (ref "R6") (pin "1") (pinfunction "1_1") (pintype "passive"))
      (node (ref "R7") (pin "1") (pinfunction "1_1") (pintype "passive"))
      (node (ref "R8") (pin "1") (pinfunction "1_1") (pintype "passive"))
      (node (ref "R9") (pin "2") (pinfunction "2_2") (pintype "passive"))
      (node (ref "U2") (pin "20") (pinfunction "VDD_20") (pintype "passive"))
      (node (ref "U4") (pin "4") (pinfunction "VOUT_4") (pintype "passive"))
      (node (ref "U4") (pin "5") (pinfunction "VOUT_5") (pintype "passive"))
    )
    (net (code "26") (name "FGND") (class "Default")
      (node (ref "J1") (pin "6") (pinfunction "SHL1_6") (pintype "passive"))
      (node (ref "J1") (pin "7") (pinfunction "SHL2_7") (pintype "passive"))
      (node (ref "J1") (pin "8") (pinfunction "SHL3_8") (pintype "passive"))
      (node (ref "J1") (pin "9") (pinfunction "SHL4_9") (pintype "passive"))
    )
    (net (code "27") (name "GND") (class "Default")
      (node (ref "C1") (pin "2") (pinfunction "2_2") (pintype "passive"))
      (node (ref "C10") (pin "1") (pinfunction "1_1") (pintype "passive"))
      (node (ref "C11") (pin "1") (pinfunction "1_1") (pintype "passive"))
      (node (ref "C12") (pin "1") (pinfunction "1_1") (pintype "passive"))
      (node (ref "C13") (pin "2") (pinfunction "2_2") (pintype "passive"))
      (node (ref "C14") (pin "1") (pinfunction "1_1") (pintype "passive"))
      (node (ref "C15") (pin "1") (pinfunction "1_1") (pintype "passive"))
      (node (ref "C16") (pin "1") (pinfunction "1_1") (pintype "passive"))
      (node (ref "C17") (pin "2") (pinfunction "2_2") (pintype "passive"))
      (node (ref "C18") (pin "2") (pinfunction "2_2") (pintype "passive"))
      (node (ref "C19") (pin "2") (pinfunction "2_2") (pintype "passive"))
      (node (ref "C2") (pin "2") (pinfunction "2_2") (pintype "passive"))
      (node (ref "C20") (pin "2") (pinfunction "2_2") (pintype "passive"))
      (node (ref "C21") (pin "2") (pinfunction "2_2") (pintype "passive"))
      (node (ref "C22") (pin "2") (pinfunction "2_2") (pintype "passive"))
      (node (ref "C23") (pin "2") (pinfunction "2_2") (pintype "passive"))
      (node (ref "C24") (pin "2") (pinfunction "2_2") (pintype "passive"))
      (node (ref "C3") (pin "2") (pinfunction "2_2") (pintype "passive"))
      (node (ref "C4") (pin "2") (pinfunction "2_2") (pintype "passive"))
      (node (ref "C5") (pin "1") (pinfunction "1_1") (pintype "passive"))
      (node (ref "C6") (pin "1") (pinfunction "1_1") (pintype "passive"))
      (node (ref "C7") (pin "2") (pinfunction "2_2") (pintype "passive"))
      (node (ref "C8") (pin "2") (pinfunction "2_2") (pintype "passive"))
      (node (ref "C9") (pin "1") (pinfunction "1_1") (pintype "passive"))
      (node (ref "D1") (pin "C") (pinfunction "C_C") (pintype "passive"))
      (node (ref "D2") (pin "C") (pinfunction "C_C") (pintype "passive"))
      (node (ref "H1") (pin "1") (pinfunction "GND_1") (pintype "passive"))
      (node (ref "H2") (pin "1") (pinfunction "GND_1") (pintype "passive"))
      (node (ref "H3") (pin "1") (pinfunction "GND_1") (pintype "passive"))
      (node (ref "H4") (pin "1") (pinfunction "GND_1") (pintype "passive"))
      (node (ref "IC1") (pin "1") (pinfunction "GND_1") (pintype "passive"))
      (node (ref "J1") (pin "5") (pinfunction "GND_5") (pintype "passive"))
      (node (ref "J10") (pin "3") (pinfunction "3_3") (pintype "passive"))
      (node (ref "J11") (pin "4") (pinfunction "4_4") (pintype "passive"))
      (node (ref "J12") (pin "3") (pinfunction "3_3") (pintype "passive"))
      (node (ref "J13") (pin "3") (pinfunction "3_3") (pintype "passive"))
      (node (ref "J14") (pin "1") (pinfunction "1_1") (pintype "passive"))
      (node (ref "J2") (pin "4") (pinfunction "4_4") (pintype "passive"))
      (node (ref "J3") (pin "3") (pinfunction "3_3") (pintype "passive"))
      (node (ref "J4") (pin "3") (pinfunction "3_3") (pintype "passive"))
      (node (ref "J5") (pin "3") (pinfunction "3_3") (pintype "passive"))
      (node (ref "J6") (pin "4") (pinfunction "4_4") (pintype "passive"))
      (node (ref "J7") (pin "3") (pinfunction "3_3") (pintype "passive"))
      (node (ref "J8") (pin "4") (pinfunction "4_4") (pintype "passive"))
      (node (ref "J9") (pin "3") (pinfunction "3_3") (pintype "passive"))
      (node (ref "P10") (pin "1") (pinfunction "1_1") (pintype "passive"))
      (node (ref "P7") (pin "4") (pinfunction "4_4") (pintype "passive"))
      (node (ref "R17") (pin "2") (pinfunction "2_2") (pintype "passive"))
      (node (ref "SW1") (pin "2") (pintype "passive"))
      (node (ref "U1") (pin "25") (pinfunction "GND_/_Exposed_Pad_25") (pintype "passive"))
      (node (ref "U1") (pin "4") (pinfunction "VSS/VREFL_4") (pintype "passive"))
      (node (ref "U2") (pin "10") (pinfunction "VSS_10") (pintype "passive"))
      (node (ref "U3") (pin "10") (pinfunction "NC_10") (pintype "passive"))
      (node (ref "U3") (pin "15") (pinfunction "PGND_15") (pintype "passive"))
      (node (ref "U3") (pin "16") (pinfunction "PGND_16") (pintype "passive"))
      (node (ref "U3") (pin "17") (pinfunction "GND-PAD_17") (pintype "passive"))
      (node (ref "U3") (pin "5") (pinfunction "GND_5") (pintype "passive"))
      (node (ref "U3") (pin "9") (pinfunction "NC_9") (pintype "passive"))
      (node (ref "U4") (pin "15") (pinfunction "PGND-PAD_15") (pintype "passive"))
      (node (ref "U4") (pin "2") (pinfunction "GND_2") (pintype "passive"))
    )
    (net (code "28") (name "Net-(C5-Pad2)") (class "Default")
      (node (ref "C5") (pin "2") (pinfunction "2_2") (pintype "passive"))
      (node (ref "J14") (pin "2") (pinfunction "2_2") (pintype "passive"))
      (node (ref "U3") (pin "11") (pinfunction "VIN_11") (pintype "passive"))
      (node (ref "U3") (pin "2") (pinfunction "VIN_2") (pintype "passive"))
    )
    (net (code "29") (name "Net-(C20-Pad1)") (class "Default")
      (node (ref "C20") (pin "1") (pinfunction "1_1") (pintype "passive"))
      (node (ref "J7") (pin "2") (pinfunction "2_2") (pintype "passive"))
    )
    (net (code "30") (name "Net-(D1-PadA)") (class "Default")
      (node (ref "D1") (pin "A") (pinfunction "A_A") (pintype "passive"))
      (node (ref "R13") (pin "2") (pinfunction "2_2") (pintype "passive"))
    )
    (net (code "31") (name "Net-(D2-PadA)") (class "Default")
      (node (ref "D2") (pin "A") (pinfunction "A_A") (pintype "passive"))
      (node (ref "R14") (pin "2") (pinfunction "2_2") (pintype "passive"))
    )
    (net (code "32") (name "Net-(D3-A)") (class "Default")
      (node (ref "C14") (pin "2") (pinfunction "2_2") (pintype "passive"))
      (node (ref "C15") (pin "2") (pinfunction "2_2") (pintype "passive"))
      (node (ref "C9") (pin "2") (pinfunction "2_2") (pintype "passive"))
      (node (ref "D3") (pin "1") (pinfunction "A_1") (pintype "passive"))
      (node (ref "Q1") (pin "2") (pinfunction "S_2") (pintype "passive"))
      (node (ref "U4") (pin "10") (pinfunction "VIN_10") (pintype "passive"))
      (node (ref "U4") (pin "11") (pinfunction "VIN_11") (pintype "passive"))
    )
    (net (code "33") (name "Net-(D3-K)") (class "Default")
      (node (ref "D3") (pin "2") (pinfunction "K_2") (pintype "passive"))
      (node (ref "J1") (pin "1") (pinfunction "VBUS_1") (pintype "passive"))
      (node (ref "Q1") (pin "1") (pinfunction "G_1") (pintype "passive"))
    )
    (net (code "34") (name "Net-(L1-Pad1)") (class "Default")
      (node (ref "L1") (pin "1") (pinfunction "1_1") (pintype "passive"))
      (node (ref "U4") (pin "8") (pinfunction "L1_8") (pintype "passive"))
      (node (ref "U4") (pin "9") (pinfunction "L1_9") (pintype "passive"))
    )
    (net (code "35") (name "Net-(L1-Pad2)") (class "Default")
      (node (ref "L1") (pin "2") (pinfunction "2_2") (pintype "passive"))
      (node (ref "U4") (pin "6") (pinfunction "L2_6") (pintype "passive"))
      (node (ref "U4") (pin "7") (pinfunction "L2_7") (pintype "passive"))
    )
    (net (code "36") (name "Net-(L2-Pad1)") (class "Default")
      (node (ref "L2") (pin "1") (pinfunction "1_1") (pintype "passive"))
      (node (ref "U3") (pin "1") (pinfunction "SW_1") (pintype "passive"))
      (node (ref "U3") (pin "14") (pinfunction "SW_14") (pintype "passive"))
    )
    (net (code "37") (name "Net-(Q1-D)") (class "Default")
      (node (ref "C6") (pin "2") (pinfunction "2_2") (pintype "passive"))
      (node (ref "C7") (pin "1") (pinfunction "1_1") (pintype "passive"))
      (node (ref "Q1") (pin "3") (pinfunction "D_3") (pintype "passive"))
      (node (ref "R12") (pin "1") (pinfunction "1_1") (pintype "passive"))
      (node (ref "U3") (pin "4") (pinfunction "VOUT_4") (pintype "passive"))
    )
    (net (code "38") (name "Net-(U1-VDD{slash}VREFH)") (class "Default")
      (node (ref "C2") (pin "1") (pinfunction "1_1") (pintype "passive"))
      (node (ref "FB1") (pin "2") (pinfunction "2_2") (pintype "passive"))
      (node (ref "U1") (pin "3") (pinfunction "VDD/VREFH_3") (pintype "passive"))
    )
    (net (code "39") (name "Net-(U2-SCL1)") (class "Default")
      (node (ref "J2") (pin "3") (pinfunction "3_3") (pintype "passive"))
      (node (ref "R1") (pin "2") (pinfunction "2_2") (pintype "passive"))
      (node (ref "U2") (pin "5") (pinfunction "SCL1_5") (pintype "passive"))
    )
    (net (code "40") (name "Net-(U2-SCL2)") (class "Default")
      (node (ref "J6") (pin "3") (pinfunction "3_3") (pintype "passive"))
      (node (ref "R3") (pin "2") (pinfunction "2_2") (pintype "passive"))
      (node (ref "U2") (pin "8") (pinfunction "SCL2_8") (pintype "passive"))
    )
    (net (code "41") (name "Net-(U2-SCL3)") (class "Default")
      (node (ref "J8") (pin "3") (pinfunction "3_3") (pintype "passive"))
      (node (ref "R5") (pin "2") (pinfunction "2_2") (pintype "passive"))
      (node (ref "U2") (pin "12") (pinfunction "SCL3_12") (pintype "passive"))
    )
    (net (code "42") (name "Net-(U2-SCL4)") (class "Default")
      (node (ref "J11") (pin "3") (pinfunction "3_3") (pintype "passive"))
      (node (ref "R7") (pin "2") (pinfunction "2_2") (pintype "passive"))
      (node (ref "U2") (pin "15") (pinfunction "SCL4_15") (pintype "passive"))
    )
    (net (code "43") (name "Net-(U2-SDA1)") (class "Default")
      (node (ref "J2") (pin "2") (pinfunction "2_2") (pintype "passive"))
      (node (ref "R2") (pin "2") (pinfunction "2_2") (pintype "passive"))
      (node (ref "U2") (pin "6") (pinfunction "SDA1_6") (pintype "passive"))
    )
    (net (code "44") (name "Net-(U2-SDA2)") (class "Default")
      (node (ref "J6") (pin "2") (pinfunction "2_2") (pintype "passive"))
      (node (ref "R4") (pin "2") (pinfunction "2_2") (pintype "passive"))
      (node (ref "U2") (pin "9") (pinfunction "SDA2_9") (pintype "passive"))
    )
    (net (code "45") (name "Net-(U2-SDA3)") (class "Default")
      (node (ref "J8") (pin "2") (pinfunction "2_2") (pintype "passive"))
      (node (ref "R6") (pin "2") (pinfunction "2_2") (pintype "passive"))
      (node (ref "U2") (pin "13") (pinfunction "SDA3_13") (pintype "passive"))
    )
    (net (code "46") (name "Net-(U2-SDA4)") (class "Default")
      (node (ref "J11") (pin "2") (pinfunction "2_2") (pintype "passive"))
      (node (ref "R8") (pin "2") (pinfunction "2_2") (pintype "passive"))
      (node (ref "U2") (pin "16") (pinfunction "SDA4_16") (pintype "passive"))
    )
    (net (code "47") (name "Net-(U3-VDD)") (class "Default")
      (node (ref "C13") (pin "1") (pinfunction "1_1") (pintype "passive"))
      (node (ref "U3") (pin "8") (pinfunction "VDD_8") (pintype "passive"))
    )
    (net (code "48") (name "Net-(U3-VSENSE)") (class "Default")
      (node (ref "L2") (pin "2") (pinfunction "2_2") (pintype "passive"))
      (node (ref "R12") (pin "2") (pinfunction "2_2") (pintype "passive"))
      (node (ref "U3") (pin "3") (pinfunction "VSENSE_3") (pintype "passive"))
    )
    (net (code "49") (name "Net-(U4-EN)") (class "Default")
      (node (ref "C16") (pin "2") (pinfunction "2_2") (pintype "passive"))
      (node (ref "U4") (pin "1") (pinfunction "VINA_1") (pintype "passive"))
      (node (ref "U4") (pin "12") (pinfunction "EN_12") (pintype "passive"))
      (node (ref "U4") (pin "13") (pinfunction "PS/SYNC_13") (pintype "passive"))
    )
    (net (code "50") (name "Net-(U4-FB)") (class "Default")
      (node (ref "R15") (pin "2") (pinfunction "2_2") (pintype "passive"))
      (node (ref "R17") (pin "1") (pinfunction "1_1") (pintype "passive"))
      (node (ref "U4") (pin "3") (pinfunction "FB_3") (pintype "passive"))
    )
    (net (code "51") (name "Net-(U4-PG)") (class "Default")
      (node (ref "R16") (pin "2") (pinfunction "2_2") (pintype "passive"))
      (node (ref "U4") (pin "14") (pinfunction "PG_14") (pintype "passive"))
    )
    (net (code "52") (name "unconnected-(IC1-GPIO0-Pad6)") (class "Default")
      (node (ref "IC1") (pin "6") (pinfunction "GPIO0_6") (pintype "passive"))
    )
    (net (code "53") (name "unconnected-(IC1-GPIO15-Pad5)") (class "Default")
      (node (ref "IC1") (pin "5") (pinfunction "GPIO15_5") (pintype "passive"))
    )
    (net (code "54") (name "unconnected-(J1-DM-Pad2)") (class "Default")
      (node (ref "J1") (pin "2") (pinfunction "DM_2") (pintype "passive+no_connect"))
    )
    (net (code "55") (name "unconnected-(J1-DP-Pad3)") (class "Default")
      (node (ref "J1") (pin "3") (pinfunction "DP_3") (pintype "passive+no_connect"))
    )
    (net (code "56") (name "unconnected-(J1-ID-Pad4)") (class "Default")
      (node (ref "J1") (pin "4") (pinfunction "ID_4") (pintype "passive+no_connect"))
    )
    (net (code "57") (name "unconnected-(U2-EXPSCL1-Pad1)") (class "Default")
      (node (ref "U2") (pin "1") (pinfunction "EXPSCL1_1") (pintype "passive"))
    )
    (net (code "58") (name "unconnected-(U2-EXPSCL2-Pad2)") (class "Default")
      (node (ref "U2") (pin "2") (pinfunction "EXPSCL2_2") (pintype "passive"))
    )
    (net (code "59") (name "unconnected-(U2-EXPSDA1-Pad18)") (class "Default")
      (node (ref "U2") (pin "18") (pinfunction "EXPSDA1_18") (pintype "passive"))
    )
    (net (code "60") (name "unconnected-(U2-EXPSDA2-Pad19)") (class "Default")
      (node (ref "U2") (pin "19") (pinfunction "EXPSDA2_19") (pintype "passive"))
    )
    (net (code "61") (name "unconnected-(U3-EN-Pad6)") (class "Default")
      (node (ref "U3") (pin "6") (pinfunction "EN_6") (pintype "passive+no_connect"))
    )
    (net (code "62") (name "unconnected-(U3-NFLT-Pad7)") (class "Default")
      (node (ref "U3") (pin "7") (pinfunction "NFLT_7") (pintype "passive+no_connect"))
    )
    (net (code "63") (name "unconnected-(U3-SCL-Pad12)") (class "Default")
      (node (ref "U3") (pin "12") (pinfunction "SCL_12") (pintype "passive"))
    )
    (net (code "64") (name "unconnected-(U3-SDA-Pad13)") (class "Default")
      (node (ref "U3") (pin "13") (pinfunction "SDA_13") (pintype "passive"))
    )
  )
)
